# M302X.net
KiCad netlist of a schematic drawn in EAGLE
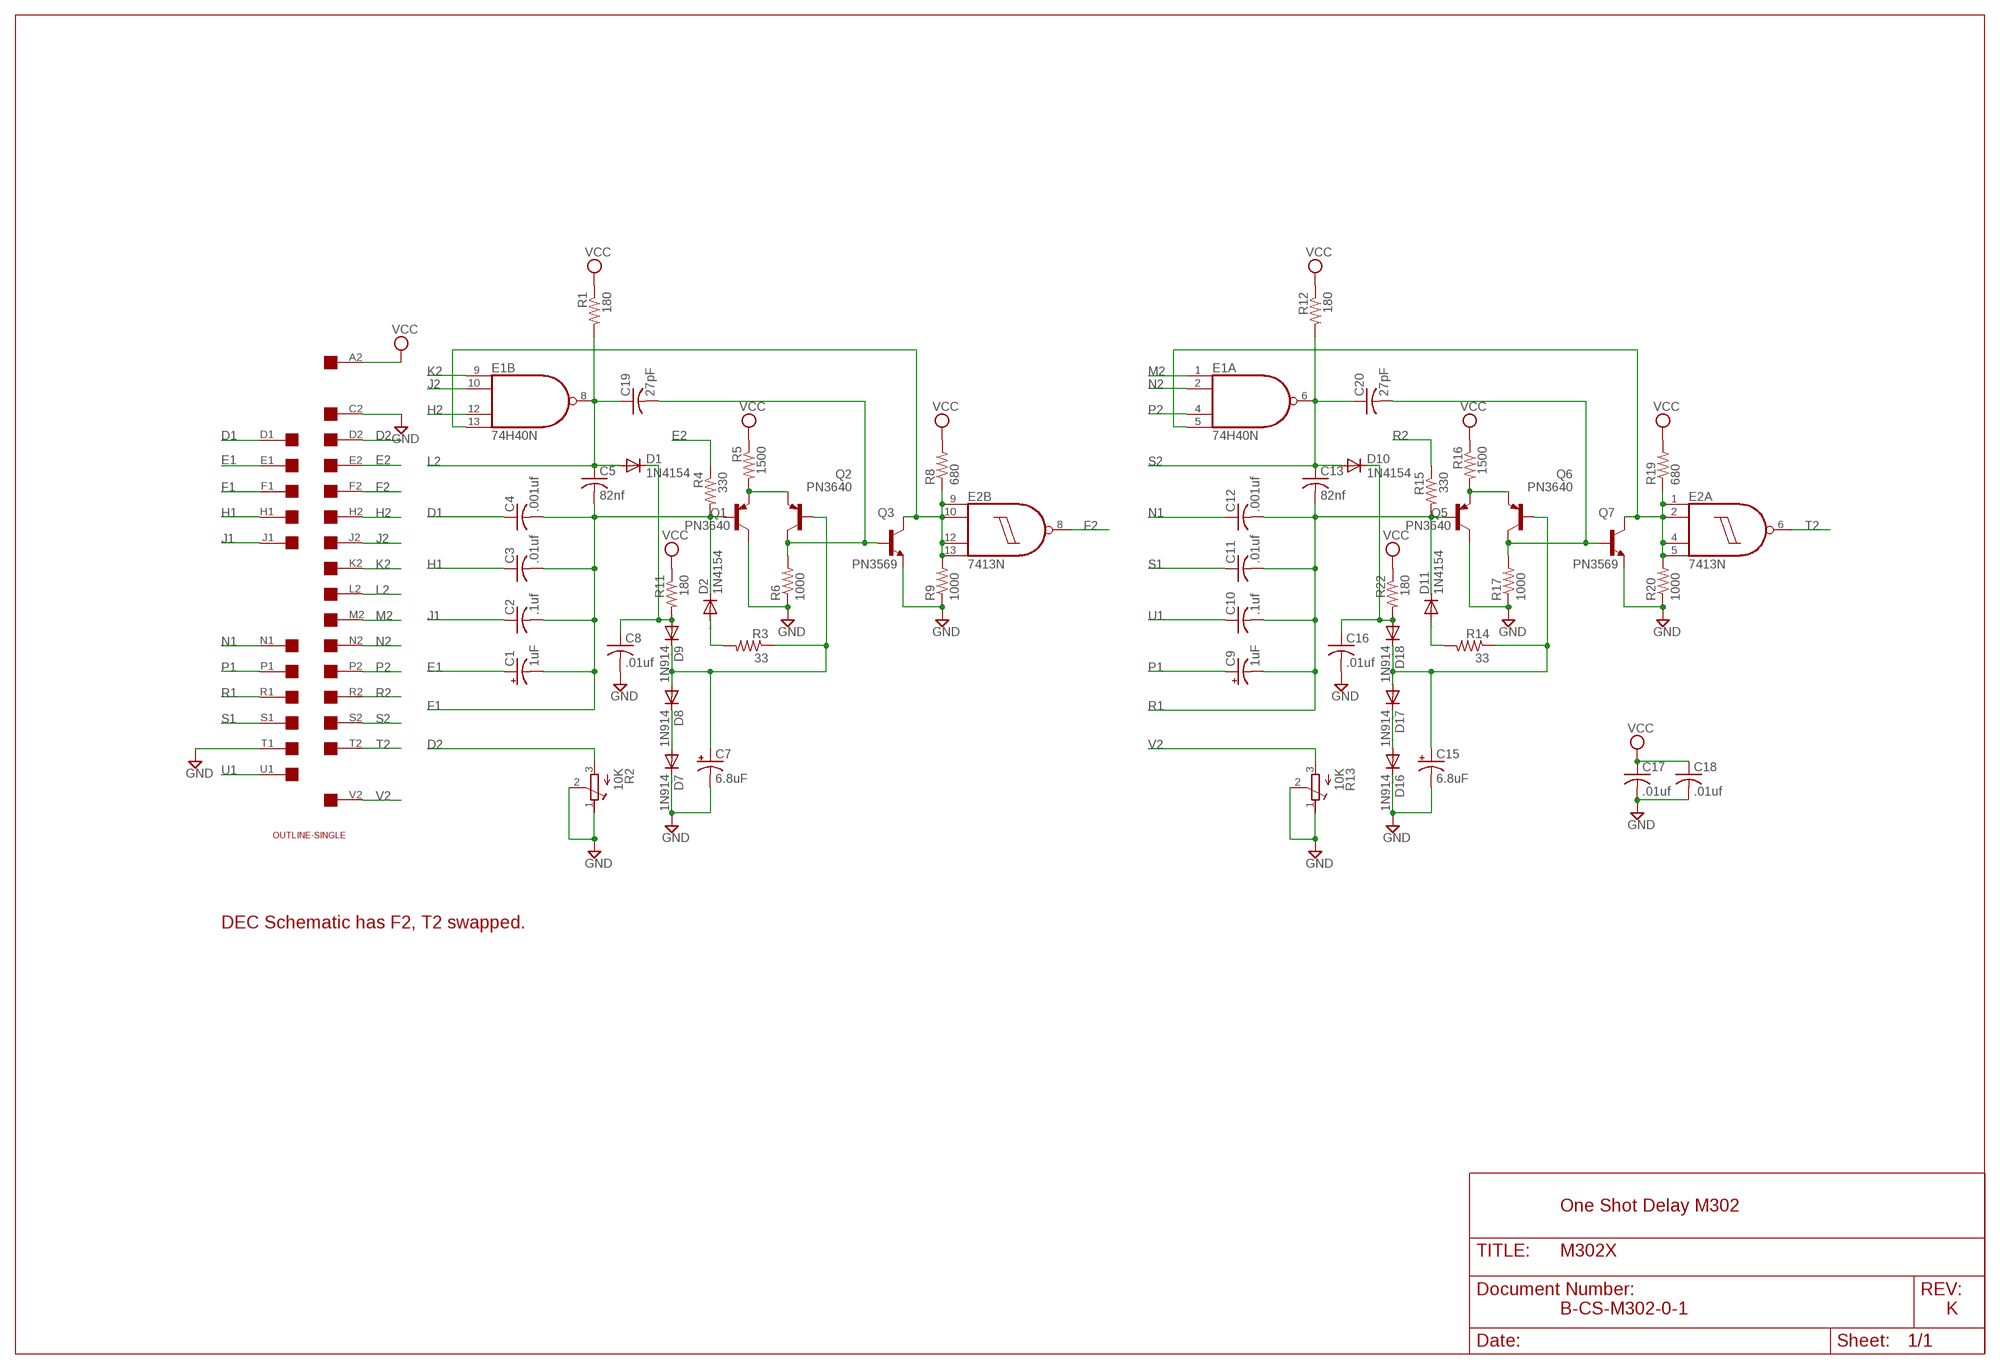
[diagram p0: schematic, sheet 1]

(export (version "E")
  (design (tool "Eeschema 10.0.6"))
  (components
    (comp (ref "C1")
      (value "1uF")
      (footprint "eagle-import:E15-5")
      (libsource (lib "eagle-import") (part "CPOL-USE15-5AXIAL"))
    )
    (comp (ref "C2")
      (value ".1uf")
      (footprint "eagle-import:C275-093X316")
      (libsource (lib "eagle-import") (part "C-US275-093X316"))
    )
    (comp (ref "C3")
      (value ".01uf")
      (footprint "eagle-import:C225-062X268")
      (libsource (lib "eagle-import") (part "C-US225-062X268"))
    )
    (comp (ref "C4")
      (value ".001uf")
      (footprint "eagle-import:C075-032X103")
      (libsource (lib "eagle-import") (part "C-US075-032X103"))
    )
    (comp (ref "C5")
      (value "82nf")
      (footprint "eagle-import:C075-032X103")
      (libsource (lib "eagle-import") (part "C-US075-032X103"))
    )
    (comp (ref "C7")
      (value "6.8uF")
      (footprint "eagle-import:E12-8")
      (libsource (lib "eagle-import") (part "CPOL-USE20-8AXIAL"))
    )
    (comp (ref "C8")
      (value ".01uf")
      (footprint "eagle-import:C050-025X075")
      (libsource (lib "eagle-import") (part "C-US050-025X075"))
    )
    (comp (ref "C9")
      (value "1uF")
      (footprint "eagle-import:E15-5")
      (libsource (lib "eagle-import") (part "CPOL-USE15-5AXIAL"))
    )
    (comp (ref "C10")
      (value ".1uf")
      (footprint "eagle-import:C275-093X316")
      (libsource (lib "eagle-import") (part "C-US275-093X316"))
    )
    (comp (ref "C11")
      (value ".01uf")
      (footprint "eagle-import:C225-062X268")
      (libsource (lib "eagle-import") (part "C-US225-062X268"))
    )
    (comp (ref "C12")
      (value ".001uf")
      (footprint "eagle-import:C075-032X103")
      (libsource (lib "eagle-import") (part "C-US075-032X103"))
    )
    (comp (ref "C13")
      (value "82nf")
      (footprint "eagle-import:C075-032X103")
      (libsource (lib "eagle-import") (part "C-US075-032X103"))
    )
    (comp (ref "C15")
      (value "6.8uF")
      (footprint "eagle-import:E12-8")
      (libsource (lib "eagle-import") (part "CPOL-USE20-8AXIAL"))
    )
    (comp (ref "C16")
      (value ".01uf")
      (footprint "eagle-import:C050-025X075")
      (libsource (lib "eagle-import") (part "C-US050-025X075"))
    )
    (comp (ref "C17")
      (value ".01uf")
      (footprint "eagle-import:C050-025X075")
      (libsource (lib "eagle-import") (part "C-US050-025X075"))
    )
    (comp (ref "C18")
      (value ".01uf")
      (footprint "eagle-import:C050-025X075")
      (libsource (lib "eagle-import") (part "C-US050-025X075"))
    )
    (comp (ref "C19")
      (value "27pF")
      (footprint "eagle-import:C075-032X103")
      (libsource (lib "eagle-import") (part "C-US075-032X103"))
    )
    (comp (ref "C20")
      (value "27pF")
      (footprint "eagle-import:C050-025X075")
      (libsource (lib "eagle-import") (part "C-US050-025X075"))
    )
    (comp (ref "D1")
      (value "1N4154")
      (footprint "eagle-import:DO35-10")
      (libsource (lib "eagle-import") (part "1N4148DO35-10"))
    )
    (comp (ref "D2")
      (value "1N4154")
      (footprint "eagle-import:DO35-10")
      (libsource (lib "eagle-import") (part "1N4148DO35-10"))
    )
    (comp (ref "D7")
      (value "1N914")
      (footprint "eagle-import:DO35-10")
      (libsource (lib "eagle-import") (part "1N4148DO35-10"))
    )
    (comp (ref "D8")
      (value "1N914")
      (footprint "eagle-import:DO35-10")
      (libsource (lib "eagle-import") (part "1N4148DO35-10"))
    )
    (comp (ref "D9")
      (value "1N914")
      (footprint "eagle-import:DO35-10")
      (libsource (lib "eagle-import") (part "1N4148DO35-10"))
    )
    (comp (ref "D10")
      (value "1N4154")
      (footprint "eagle-import:DO35-10")
      (libsource (lib "eagle-import") (part "1N4148DO35-10"))
    )
    (comp (ref "D11")
      (value "1N4154")
      (footprint "eagle-import:DO35-10")
      (libsource (lib "eagle-import") (part "1N4148DO35-10"))
    )
    (comp (ref "D16")
      (value "1N914")
      (footprint "eagle-import:DO35-10")
      (libsource (lib "eagle-import") (part "1N4148DO35-10"))
    )
    (comp (ref "D17")
      (value "1N914")
      (footprint "eagle-import:DO35-10")
      (libsource (lib "eagle-import") (part "1N4148DO35-10"))
    )
    (comp (ref "D18")
      (value "1N914")
      (footprint "eagle-import:DO35-10")
      (libsource (lib "eagle-import") (part "1N4148DO35-10"))
    )
    (comp (ref "E1")
      (value "74H40N")
      (footprint "eagle-import:DIL14")
      (libsource (lib "eagle-import") (part "7420NS"))
    )
    (comp (ref "E2")
      (value "7413N")
      (footprint "eagle-import:DIL14")
      (libsource (lib "eagle-import") (part "7413N"))
    )
    (comp (ref "Q1")
      (value "PN3640")
      (footprint "eagle-import:TO39")
      (libsource (lib "eagle-import") (part "-PNP-TO39-EBC2N3637"))
    )
    (comp (ref "Q2")
      (value "PN3640")
      (footprint "eagle-import:TO39")
      (libsource (lib "eagle-import") (part "-PNP-TO39-EBC2N3637"))
    )
    (comp (ref "Q3")
      (value "PN3569")
      (footprint "eagle-import:TO39")
      (libsource (lib "eagle-import") (part "-NPN-TO39-EBC2N3019"))
    )
    (comp (ref "Q5")
      (value "PN3640")
      (footprint "eagle-import:TO39")
      (libsource (lib "eagle-import") (part "-PNP-TO39-EBC2N3637"))
    )
    (comp (ref "Q6")
      (value "PN3640")
      (footprint "eagle-import:TO39")
      (libsource (lib "eagle-import") (part "-PNP-TO39-EBC2N3637"))
    )
    (comp (ref "Q7")
      (value "PN3569")
      (footprint "eagle-import:TO39")
      (libsource (lib "eagle-import") (part "-NPN-TO39-EBC2N3019"))
    )
    (comp (ref "R1")
      (value "180")
      (footprint "eagle-import:0207_10")
      (libsource (lib "eagle-import") (part "R-US_0207/10"))
    )
    (comp (ref "R2")
      (value "10K")
      (footprint "eagle-import:3006Y")
      (libsource (lib "eagle-import") (part "275P"))
    )
    (comp (ref "R3")
      (value "33")
      (footprint "eagle-import:0207_10")
      (libsource (lib "eagle-import") (part "R-US_0207/10"))
    )
    (comp (ref "R4")
      (value "330")
      (footprint "eagle-import:0207_10")
      (libsource (lib "eagle-import") (part "R-US_0207/10"))
    )
    (comp (ref "R5")
      (value "1500")
      (footprint "eagle-import:0207_10")
      (libsource (lib "eagle-import") (part "R-US_0207/10"))
    )
    (comp (ref "R6")
      (value "1000")
      (footprint "eagle-import:0207_10")
      (libsource (lib "eagle-import") (part "R-US_0207/10"))
    )
    (comp (ref "R8")
      (value "680")
      (footprint "eagle-import:0207_10")
      (libsource (lib "eagle-import") (part "R-US_0207/10"))
    )
    (comp (ref "R9")
      (value "1000")
      (footprint "eagle-import:0207_10")
      (libsource (lib "eagle-import") (part "R-US_0207/10"))
    )
    (comp (ref "R11")
      (value "180")
      (footprint "eagle-import:0207_10")
      (libsource (lib "eagle-import") (part "R-US_0207/10"))
    )
    (comp (ref "R12")
      (value "180")
      (footprint "eagle-import:0207_10")
      (libsource (lib "eagle-import") (part "R-US_0207/10"))
    )
    (comp (ref "R13")
      (value "10K")
      (footprint "eagle-import:3006Y")
      (libsource (lib "eagle-import") (part "275P"))
    )
    (comp (ref "R14")
      (value "33")
      (footprint "eagle-import:0207_10")
      (libsource (lib "eagle-import") (part "R-US_0207/10"))
    )
    (comp (ref "R15")
      (value "330")
      (footprint "eagle-import:0207_10")
      (libsource (lib "eagle-import") (part "R-US_0207/10"))
    )
    (comp (ref "R16")
      (value "1500")
      (footprint "eagle-import:0207_10")
      (libsource (lib "eagle-import") (part "R-US_0207/10"))
    )
    (comp (ref "R17")
      (value "1000")
      (footprint "eagle-import:0207_10")
      (libsource (lib "eagle-import") (part "R-US_0207/10"))
    )
    (comp (ref "R19")
      (value "680")
      (footprint "eagle-import:0207_10")
      (libsource (lib "eagle-import") (part "R-US_0207/10"))
    )
    (comp (ref "R20")
      (value "1000")
      (footprint "eagle-import:0207_10")
      (libsource (lib "eagle-import") (part "R-US_0207/10"))
    )
    (comp (ref "R22")
      (value "180")
      (footprint "eagle-import:0207_10")
      (libsource (lib "eagle-import") (part "R-US_0207/10"))
    )
    (comp (ref "U$1")
      (value "SINGLE")
      (footprint "eagle-import:EDGE-CON2")
      (libsource (lib "eagle-import") (part "SINGLE"))
    )
    (comp (ref "U$2")
      (value "OUTLINE-SINGLE")
      (footprint "eagle-import:SINGLE")
      (libsource (lib "eagle-import") (part "OUTLINE-SINGLE"))
    )
  )
  (nets
    (net (code "1") (name "/D1") (class "Default")
      (node (ref "C4") (pin "1") (pinfunction "1_1") (pintype "passive"))
      (node (ref "U$1") (pin "D1") (pinfunction "1_D1") (pintype "bidirectional"))
    )
    (net (code "2") (name "/D2") (class "Default")
      (node (ref "R2") (pin "3") (pinfunction "E_3") (pintype "passive"))
      (node (ref "U$1") (pin "D2") (pinfunction "1_D2") (pintype "bidirectional"))
    )
    (net (code "3") (name "/E1") (class "Default")
      (node (ref "C1") (pin "+") (pinfunction "+_+") (pintype "passive"))
      (node (ref "U$1") (pin "E1") (pinfunction "1_E1") (pintype "bidirectional"))
    )
    (net (code "4") (name "/E2") (class "Default")
      (node (ref "R4") (pin "1") (pinfunction "1_1") (pintype "passive"))
      (node (ref "U$1") (pin "E2") (pinfunction "1_E2") (pintype "bidirectional"))
    )
    (net (code "5") (name "/F1") (class "Default")
      (node (ref "C1") (pin "-") (pinfunction "-_-") (pintype "passive"))
      (node (ref "C2") (pin "2") (pinfunction "2_2") (pintype "passive"))
      (node (ref "C3") (pin "2") (pinfunction "2_2") (pintype "passive"))
      (node (ref "C4") (pin "2") (pinfunction "2_2") (pintype "passive"))
      (node (ref "C5") (pin "2") (pinfunction "2_2") (pintype "passive"))
      (node (ref "D2") (pin "C") (pinfunction "C_C") (pintype "passive"))
      (node (ref "Q1") (pin "2") (pinfunction "B_2") (pintype "passive"))
      (node (ref "R4") (pin "2") (pinfunction "2_2") (pintype "passive"))
      (node (ref "U$1") (pin "F1") (pinfunction "1_F1") (pintype "bidirectional"))
    )
    (net (code "6") (name "/F2") (class "Default")
      (node (ref "E2") (pin "8") (pinfunction "O_8") (pintype "output"))
      (node (ref "U$1") (pin "F2") (pinfunction "1_F2") (pintype "bidirectional"))
    )
    (net (code "7") (name "/H1") (class "Default")
      (node (ref "C3") (pin "1") (pinfunction "1_1") (pintype "passive"))
      (node (ref "U$1") (pin "H1") (pinfunction "1_H1") (pintype "bidirectional"))
    )
    (net (code "8") (name "/H2") (class "Default")
      (node (ref "E1") (pin "12") (pinfunction "I2_12") (pintype "input"))
      (node (ref "U$1") (pin "H2") (pinfunction "1_H2") (pintype "bidirectional"))
    )
    (net (code "9") (name "/J1") (class "Default")
      (node (ref "C2") (pin "1") (pinfunction "1_1") (pintype "passive"))
      (node (ref "U$1") (pin "J1") (pinfunction "1_J1") (pintype "bidirectional"))
    )
    (net (code "10") (name "/J2") (class "Default")
      (node (ref "E1") (pin "10") (pinfunction "I1_10") (pintype "input"))
      (node (ref "U$1") (pin "J2") (pinfunction "1_J2") (pintype "bidirectional"))
    )
    (net (code "11") (name "/K2") (class "Default")
      (node (ref "E1") (pin "9") (pinfunction "I0_9") (pintype "input"))
      (node (ref "U$1") (pin "K2") (pinfunction "1_K2") (pintype "bidirectional"))
    )
    (net (code "12") (name "/L2") (class "Default")
      (node (ref "C19") (pin "1") (pinfunction "1_1") (pintype "passive"))
      (node (ref "C5") (pin "1") (pinfunction "1_1") (pintype "passive"))
      (node (ref "D1") (pin "A") (pinfunction "A_A") (pintype "passive"))
      (node (ref "E1") (pin "8") (pinfunction "O_8") (pintype "output"))
      (node (ref "R1") (pin "2") (pinfunction "2_2") (pintype "passive"))
      (node (ref "U$1") (pin "L2") (pinfunction "1_L2") (pintype "bidirectional"))
    )
    (net (code "13") (name "/M2") (class "Default")
      (node (ref "E1") (pin "1") (pinfunction "I0_1") (pintype "input"))
      (node (ref "U$1") (pin "M2") (pinfunction "1_M2") (pintype "bidirectional"))
    )
    (net (code "14") (name "/N1") (class "Default")
      (node (ref "C12") (pin "1") (pinfunction "1_1") (pintype "passive"))
      (node (ref "U$1") (pin "N1") (pinfunction "1_N1") (pintype "bidirectional"))
    )
    (net (code "15") (name "/N2") (class "Default")
      (node (ref "E1") (pin "2") (pinfunction "I1_2") (pintype "input"))
      (node (ref "U$1") (pin "N2") (pinfunction "1_N2") (pintype "bidirectional"))
    )
    (net (code "16") (name "/P1") (class "Default")
      (node (ref "C9") (pin "+") (pinfunction "+_+") (pintype "passive"))
      (node (ref "U$1") (pin "P1") (pinfunction "1_P1") (pintype "bidirectional"))
    )
    (net (code "17") (name "/P2") (class "Default")
      (node (ref "E1") (pin "4") (pinfunction "I2_4") (pintype "input"))
      (node (ref "U$1") (pin "P2") (pinfunction "1_P2") (pintype "bidirectional"))
    )
    (net (code "18") (name "/R1") (class "Default")
      (node (ref "C10") (pin "2") (pinfunction "2_2") (pintype "passive"))
      (node (ref "C11") (pin "2") (pinfunction "2_2") (pintype "passive"))
      (node (ref "C12") (pin "2") (pinfunction "2_2") (pintype "passive"))
      (node (ref "C13") (pin "2") (pinfunction "2_2") (pintype "passive"))
      (node (ref "C9") (pin "-") (pinfunction "-_-") (pintype "passive"))
      (node (ref "D11") (pin "C") (pinfunction "C_C") (pintype "passive"))
      (node (ref "Q5") (pin "2") (pinfunction "B_2") (pintype "passive"))
      (node (ref "R15") (pin "2") (pinfunction "2_2") (pintype "passive"))
      (node (ref "U$1") (pin "R1") (pinfunction "1_R1") (pintype "bidirectional"))
    )
    (net (code "19") (name "/R2") (class "Default")
      (node (ref "R15") (pin "1") (pinfunction "1_1") (pintype "passive"))
      (node (ref "U$1") (pin "R2") (pinfunction "1_R2") (pintype "bidirectional"))
    )
    (net (code "20") (name "/S1") (class "Default")
      (node (ref "C11") (pin "1") (pinfunction "1_1") (pintype "passive"))
      (node (ref "U$1") (pin "S1") (pinfunction "1_S1") (pintype "bidirectional"))
    )
    (net (code "21") (name "/S2") (class "Default")
      (node (ref "C13") (pin "1") (pinfunction "1_1") (pintype "passive"))
      (node (ref "C20") (pin "1") (pinfunction "1_1") (pintype "passive"))
      (node (ref "D10") (pin "A") (pinfunction "A_A") (pintype "passive"))
      (node (ref "E1") (pin "6") (pinfunction "O_6") (pintype "output"))
      (node (ref "R12") (pin "2") (pinfunction "2_2") (pintype "passive"))
      (node (ref "U$1") (pin "S2") (pinfunction "1_S2") (pintype "bidirectional"))
    )
    (net (code "22") (name "/T2") (class "Default")
      (node (ref "E2") (pin "6") (pinfunction "O_6") (pintype "output"))
      (node (ref "U$1") (pin "T2") (pinfunction "1_T2") (pintype "bidirectional"))
    )
    (net (code "23") (name "/U1") (class "Default")
      (node (ref "C10") (pin "1") (pinfunction "1_1") (pintype "passive"))
      (node (ref "U$1") (pin "U1") (pinfunction "1_U1") (pintype "bidirectional"))
    )
    (net (code "24") (name "/V2") (class "Default")
      (node (ref "R13") (pin "3") (pinfunction "E_3") (pintype "passive"))
      (node (ref "U$1") (pin "V2") (pinfunction "1_V2") (pintype "bidirectional"))
    )
    (net (code "25") (name "GND") (class "Default")
      (node (ref "C15") (pin "-") (pinfunction "-_-") (pintype "passive"))
      (node (ref "C16") (pin "2") (pinfunction "2_2") (pintype "passive"))
      (node (ref "C17") (pin "2") (pinfunction "2_2") (pintype "passive"))
      (node (ref "C18") (pin "2") (pinfunction "2_2") (pintype "passive"))
      (node (ref "C7") (pin "-") (pinfunction "-_-") (pintype "passive"))
      (node (ref "C8") (pin "2") (pinfunction "2_2") (pintype "passive"))
      (node (ref "D16") (pin "C") (pinfunction "C_C") (pintype "passive"))
      (node (ref "D7") (pin "C") (pinfunction "C_C") (pintype "passive"))
      (node (ref "Q1") (pin "3") (pinfunction "C_3") (pintype "passive"))
      (node (ref "Q3") (pin "1") (pinfunction "E_1") (pintype "passive"))
      (node (ref "Q5") (pin "3") (pinfunction "C_3") (pintype "passive"))
      (node (ref "Q7") (pin "1") (pinfunction "E_1") (pintype "passive"))
      (node (ref "R13") (pin "1") (pinfunction "A_1") (pintype "passive"))
      (node (ref "R13") (pin "2") (pinfunction "S_2") (pintype "passive"))
      (node (ref "R17") (pin "1") (pinfunction "1_1") (pintype "passive"))
      (node (ref "R2") (pin "1") (pinfunction "A_1") (pintype "passive"))
      (node (ref "R2") (pin "2") (pinfunction "S_2") (pintype "passive"))
      (node (ref "R20") (pin "1") (pinfunction "1_1") (pintype "passive"))
      (node (ref "R6") (pin "1") (pinfunction "1_1") (pintype "passive"))
      (node (ref "R9") (pin "1") (pinfunction "1_1") (pintype "passive"))
      (node (ref "U$1") (pin "C2") (pinfunction "1_C2") (pintype "bidirectional"))
      (node (ref "U$1") (pin "T1") (pinfunction "1_T1") (pintype "bidirectional"))
    )
    (net (code "26") (name "Net-(C8-Pad1)") (class "Default")
      (node (ref "C8") (pin "1") (pinfunction "1_1") (pintype "passive"))
      (node (ref "D1") (pin "C") (pinfunction "C_C") (pintype "passive"))
      (node (ref "D9") (pin "A") (pinfunction "A_A") (pintype "passive"))
      (node (ref "R11") (pin "2") (pinfunction "2_2") (pintype "passive"))
    )
    (net (code "27") (name "Net-(C16-Pad1)") (class "Default")
      (node (ref "C16") (pin "1") (pinfunction "1_1") (pintype "passive"))
      (node (ref "D10") (pin "C") (pinfunction "C_C") (pintype "passive"))
      (node (ref "D18") (pin "A") (pinfunction "A_A") (pintype "passive"))
      (node (ref "R22") (pin "2") (pinfunction "2_2") (pintype "passive"))
    )
    (net (code "28") (name "Net-(D2-PadA)") (class "Default")
      (node (ref "D2") (pin "A") (pinfunction "A_A") (pintype "passive"))
      (node (ref "R3") (pin "2") (pinfunction "2_2") (pintype "passive"))
    )
    (net (code "29") (name "Net-(D7-PadA)") (class "Default")
      (node (ref "D7") (pin "A") (pinfunction "A_A") (pintype "passive"))
      (node (ref "D8") (pin "C") (pinfunction "C_C") (pintype "passive"))
    )
    (net (code "30") (name "Net-(D11-PadA)") (class "Default")
      (node (ref "D11") (pin "A") (pinfunction "A_A") (pintype "passive"))
      (node (ref "R14") (pin "2") (pinfunction "2_2") (pintype "passive"))
    )
    (net (code "31") (name "Net-(D16-PadA)") (class "Default")
      (node (ref "D16") (pin "A") (pinfunction "A_A") (pintype "passive"))
      (node (ref "D17") (pin "C") (pinfunction "C_C") (pintype "passive"))
    )
    (net (code "32") (name "Net-(E1A-I3)") (class "Default")
      (node (ref "E1") (pin "5") (pinfunction "I3_5") (pintype "input"))
      (node (ref "E2") (pin "1") (pinfunction "I0_1") (pintype "input"))
      (node (ref "E2") (pin "2") (pinfunction "I1_2") (pintype "input"))
      (node (ref "E2") (pin "4") (pinfunction "I2_4") (pintype "input"))
      (node (ref "E2") (pin "5") (pinfunction "I3_5") (pintype "input"))
      (node (ref "Q7") (pin "3") (pinfunction "C_3") (pintype "passive"))
      (node (ref "R19") (pin "1") (pinfunction "1_1") (pintype "passive"))
      (node (ref "R20") (pin "2") (pinfunction "2_2") (pintype "passive"))
    )
    (net (code "33") (name "Net-(E1B-I3)") (class "Default")
      (node (ref "E1") (pin "13") (pinfunction "I3_13") (pintype "input"))
      (node (ref "E2") (pin "10") (pinfunction "I1_10") (pintype "input"))
      (node (ref "E2") (pin "12") (pinfunction "I2_12") (pintype "input"))
      (node (ref "E2") (pin "13") (pinfunction "I3_13") (pintype "input"))
      (node (ref "E2") (pin "9") (pinfunction "I0_9") (pintype "input"))
      (node (ref "Q3") (pin "3") (pinfunction "C_3") (pintype "passive"))
      (node (ref "R8") (pin "1") (pinfunction "1_1") (pintype "passive"))
      (node (ref "R9") (pin "2") (pinfunction "2_2") (pintype "passive"))
    )
    (net (code "34") (name "Net-(Q1-E)") (class "Default")
      (node (ref "Q1") (pin "1") (pinfunction "E_1") (pintype "passive"))
      (node (ref "Q2") (pin "1") (pinfunction "E_1") (pintype "passive"))
      (node (ref "R5") (pin "2") (pinfunction "2_2") (pintype "passive"))
    )
    (net (code "35") (name "Net-(Q2-B)") (class "Default")
      (node (ref "C7") (pin "+") (pinfunction "+_+") (pintype "passive"))
      (node (ref "D8") (pin "A") (pinfunction "A_A") (pintype "passive"))
      (node (ref "D9") (pin "C") (pinfunction "C_C") (pintype "passive"))
      (node (ref "Q2") (pin "2") (pinfunction "B_2") (pintype "passive"))
      (node (ref "R3") (pin "1") (pinfunction "1_1") (pintype "passive"))
    )
    (net (code "36") (name "Net-(Q2-C)") (class "Default")
      (node (ref "C19") (pin "2") (pinfunction "2_2") (pintype "passive"))
      (node (ref "Q2") (pin "3") (pinfunction "C_3") (pintype "passive"))
      (node (ref "Q3") (pin "2") (pinfunction "B_2") (pintype "passive"))
      (node (ref "R6") (pin "2") (pinfunction "2_2") (pintype "passive"))
    )
    (net (code "37") (name "Net-(Q5-E)") (class "Default")
      (node (ref "Q5") (pin "1") (pinfunction "E_1") (pintype "passive"))
      (node (ref "Q6") (pin "1") (pinfunction "E_1") (pintype "passive"))
      (node (ref "R16") (pin "2") (pinfunction "2_2") (pintype "passive"))
    )
    (net (code "38") (name "Net-(Q6-B)") (class "Default")
      (node (ref "C15") (pin "+") (pinfunction "+_+") (pintype "passive"))
      (node (ref "D17") (pin "A") (pinfunction "A_A") (pintype "passive"))
      (node (ref "D18") (pin "C") (pinfunction "C_C") (pintype "passive"))
      (node (ref "Q6") (pin "2") (pinfunction "B_2") (pintype "passive"))
      (node (ref "R14") (pin "1") (pinfunction "1_1") (pintype "passive"))
    )
    (net (code "39") (name "Net-(Q6-C)") (class "Default")
      (node (ref "C20") (pin "2") (pinfunction "2_2") (pintype "passive"))
      (node (ref "Q6") (pin "3") (pinfunction "C_3") (pintype "passive"))
      (node (ref "Q7") (pin "2") (pinfunction "B_2") (pintype "passive"))
      (node (ref "R17") (pin "2") (pinfunction "2_2") (pintype "passive"))
    )
    (net (code "40") (name "VCC") (class "Default")
      (node (ref "C17") (pin "1") (pinfunction "1_1") (pintype "passive"))
      (node (ref "C18") (pin "1") (pinfunction "1_1") (pintype "passive"))
      (node (ref "R1") (pin "1") (pinfunction "1_1") (pintype "passive"))
      (node (ref "R11") (pin "1") (pinfunction "1_1") (pintype "passive"))
      (node (ref "R12") (pin "1") (pinfunction "1_1") (pintype "passive"))
      (node (ref "R16") (pin "1") (pinfunction "1_1") (pintype "passive"))
      (node (ref "R19") (pin "2") (pinfunction "2_2") (pintype "passive"))
      (node (ref "R22") (pin "1") (pinfunction "1_1") (pintype "passive"))
      (node (ref "R5") (pin "1") (pinfunction "1_1") (pintype "passive"))
      (node (ref "R8") (pin "2") (pinfunction "2_2") (pintype "passive"))
      (node (ref "U$1") (pin "A2") (pinfunction "1_A2") (pintype "bidirectional"))
    )
  )
)
